# Sheet4.net
KiCad netlist of a schematic drawn in Altium Designer
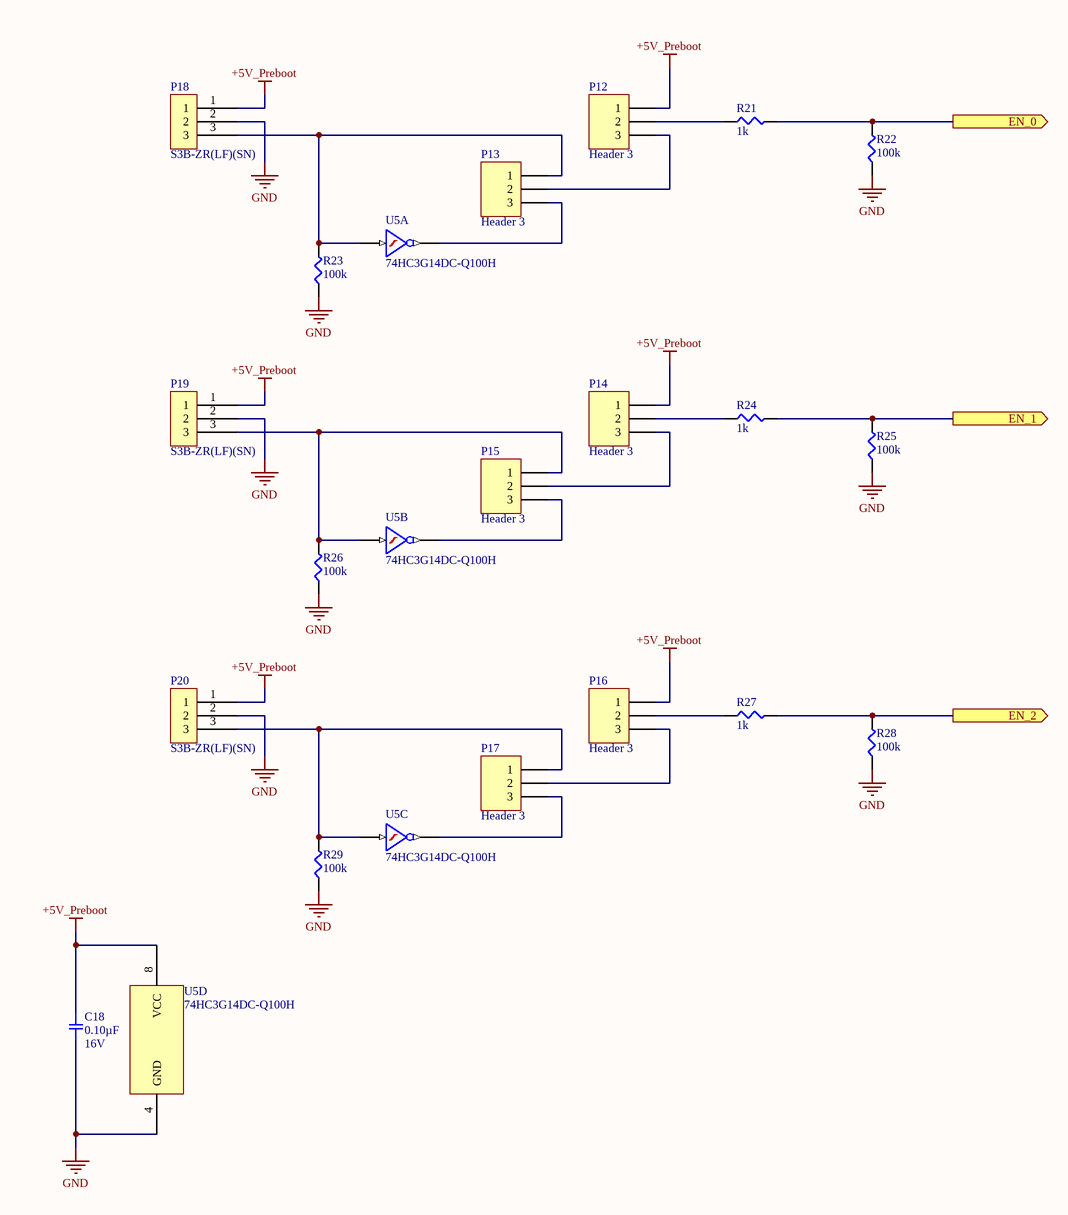
[diagram p0: Sheet4.SchDoc]

(export (version "E")
  (design (tool "Eeschema 10.0.6"))
  (components
    (comp (ref "C18")
      (value "0.10µF")
      (footprint "SMD-0402C")
      (description "CAP CER 0.1UF 16V X7R 0402")
      (fields
        (field (name "DIGI-KEY PART NUMBER") "490-4759-1-ND")
        (field (name "PART NUMBER") "GCM155R71C104KA55D")
        (field (name "VOLTAGE") "16V")
      )
      (libsource (lib "capacitor_murata_0402") (part "GCM155R71C104KA55D"))
    )
    (comp (ref "P12")
      (value "Header 3")
      (footprint "HDR1X3")
      (description "Header, 3-Pin")
      (fields (field (name "PUBLISHER") "Altium Limited"))
      (libsource (lib "Miscellaneous Connectors") (part "Header 3"))
    )
    (comp (ref "P13")
      (value "Header 3")
      (footprint "HDR1X3")
      (description "Header, 3-Pin")
      (fields (field (name "PUBLISHER") "Altium Limited"))
      (libsource (lib "Miscellaneous Connectors") (part "Header 3"))
    )
    (comp (ref "P14")
      (value "Header 3")
      (footprint "HDR1X3")
      (description "Header, 3-Pin")
      (fields (field (name "PUBLISHER") "Altium Limited"))
      (libsource (lib "Miscellaneous Connectors") (part "Header 3"))
    )
    (comp (ref "P15")
      (value "Header 3")
      (footprint "HDR1X3")
      (description "Header, 3-Pin")
      (fields (field (name "PUBLISHER") "Altium Limited"))
      (libsource (lib "Miscellaneous Connectors") (part "Header 3"))
    )
    (comp (ref "P16")
      (value "Header 3")
      (footprint "HDR1X3")
      (description "Header, 3-Pin")
      (fields (field (name "PUBLISHER") "Altium Limited"))
      (libsource (lib "Miscellaneous Connectors") (part "Header 3"))
    )
    (comp (ref "P17")
      (value "Header 3")
      (footprint "HDR1X3")
      (description "Header, 3-Pin")
      (fields (field (name "PUBLISHER") "Altium Limited"))
      (libsource (lib "Miscellaneous Connectors") (part "Header 3"))
    )
    (comp (ref "P18")
      (value "S3B-ZR(LF)(SN)")
      (footprint "S3B-ZR(LF)(SN)")
      (libsource (lib "ModularPayload") (part "S3B-ZR(LF)(SN)"))
    )
    (comp (ref "P19")
      (value "S3B-ZR(LF)(SN)")
      (footprint "S3B-ZR(LF)(SN)")
      (libsource (lib "ModularPayload") (part "S3B-ZR(LF)(SN)"))
    )
    (comp (ref "P20")
      (value "S3B-ZR(LF)(SN)")
      (footprint "S3B-ZR(LF)(SN)")
      (libsource (lib "ModularPayload") (part "S3B-ZR(LF)(SN)"))
    )
    (comp (ref "R21")
      (value "1k")
      (footprint "SMD-0402-RES")
      (description "RES SMD 1K OHM 5% 1/10W 0402")
      (fields (field (name "PART NUMBER") "ERJ-2GEJ102X") (field (name "DIGI-KEY PART NUMBER") "P1.0KJCT-ND"))
      (libsource (lib "Panasonic_ERJ_0402") (part "ERJ-2GEJ102X"))
    )
    (comp (ref "R22")
      (value "100k")
      (footprint "SMD-0402-RES")
      (description "RES SMD 100K OHM 5% 1/10W 0402")
      (fields (field (name "PART NUMBER") "ERJ-2GEJ104X") (field (name "DIGI-KEY PART NUMBER") "P100KJCT-ND"))
      (libsource (lib "Panasonic_ERJ_0402") (part "ERJ-2GEJ104X"))
    )
    (comp (ref "R23")
      (value "100k")
      (footprint "SMD-0402-RES")
      (description "RES SMD 100K OHM 5% 1/10W 0402")
      (fields (field (name "PART NUMBER") "ERJ-2GEJ104X") (field (name "DIGI-KEY PART NUMBER") "P100KJCT-ND"))
      (libsource (lib "Panasonic_ERJ_0402") (part "ERJ-2GEJ104X"))
    )
    (comp (ref "R24")
      (value "1k")
      (footprint "SMD-0402-RES")
      (description "RES SMD 1K OHM 5% 1/10W 0402")
      (fields (field (name "PART NUMBER") "ERJ-2GEJ102X") (field (name "DIGI-KEY PART NUMBER") "P1.0KJCT-ND"))
      (libsource (lib "Panasonic_ERJ_0402") (part "ERJ-2GEJ102X"))
    )
    (comp (ref "R25")
      (value "100k")
      (footprint "SMD-0402-RES")
      (description "RES SMD 100K OHM 5% 1/10W 0402")
      (fields (field (name "PART NUMBER") "ERJ-2GEJ104X") (field (name "DIGI-KEY PART NUMBER") "P100KJCT-ND"))
      (libsource (lib "Panasonic_ERJ_0402") (part "ERJ-2GEJ104X"))
    )
    (comp (ref "R26")
      (value "100k")
      (footprint "SMD-0402-RES")
      (description "RES SMD 100K OHM 5% 1/10W 0402")
      (fields (field (name "PART NUMBER") "ERJ-2GEJ104X") (field (name "DIGI-KEY PART NUMBER") "P100KJCT-ND"))
      (libsource (lib "Panasonic_ERJ_0402") (part "ERJ-2GEJ104X"))
    )
    (comp (ref "R27")
      (value "1k")
      (footprint "SMD-0402-RES")
      (description "RES SMD 1K OHM 5% 1/10W 0402")
      (fields (field (name "PART NUMBER") "ERJ-2GEJ102X") (field (name "DIGI-KEY PART NUMBER") "P1.0KJCT-ND"))
      (libsource (lib "Panasonic_ERJ_0402") (part "ERJ-2GEJ102X"))
    )
    (comp (ref "R28")
      (value "100k")
      (footprint "SMD-0402-RES")
      (description "RES SMD 100K OHM 5% 1/10W 0402")
      (fields (field (name "PART NUMBER") "ERJ-2GEJ104X") (field (name "DIGI-KEY PART NUMBER") "P100KJCT-ND"))
      (libsource (lib "Panasonic_ERJ_0402") (part "ERJ-2GEJ104X"))
    )
    (comp (ref "R29")
      (value "100k")
      (footprint "SMD-0402-RES")
      (description "RES SMD 100K OHM 5% 1/10W 0402")
      (fields (field (name "PART NUMBER") "ERJ-2GEJ104X") (field (name "DIGI-KEY PART NUMBER") "P100KJCT-ND"))
      (libsource (lib "Panasonic_ERJ_0402") (part "ERJ-2GEJ104X"))
    )
    (comp (ref "U5")
      (value "74HC3G14DC-Q100H")
      (footprint "TSSOP50P310X100-8N (74HC3G14DC-Q100H)")
      (libsource (lib "ModularPayload") (part "74HC3G14DC-Q100H"))
    )
  )
  (nets
    (net (code "1") (name "+5V_Preboot") (class "Default")
      (node (ref "C18") (pin "1") (pinfunction "1_1") (pintype "passive"))
      (node (ref "P12") (pin "1") (pinfunction "1_1") (pintype "passive"))
      (node (ref "P14") (pin "1") (pinfunction "1_1") (pintype "passive"))
      (node (ref "P16") (pin "1") (pinfunction "1_1") (pintype "passive"))
      (node (ref "P18") (pin "1") (pinfunction "1_1") (pintype "passive"))
      (node (ref "P19") (pin "1") (pinfunction "1_1") (pintype "passive"))
      (node (ref "P20") (pin "1") (pinfunction "1_1") (pintype "passive"))
      (node (ref "U5") (pin "8") (pinfunction "VCC_8") (pintype "passive"))
    )
    (net (code "2") (name "/EN_0") (class "Default")
      (node (ref "R21") (pin "2") (pinfunction "2_2") (pintype "passive"))
      (node (ref "R22") (pin "2") (pinfunction "2_2") (pintype "passive"))
    )
    (net (code "3") (name "/EN_1") (class "Default")
      (node (ref "R24") (pin "2") (pinfunction "2_2") (pintype "passive"))
      (node (ref "R25") (pin "2") (pinfunction "2_2") (pintype "passive"))
    )
    (net (code "4") (name "/EN_2") (class "Default")
      (node (ref "R27") (pin "2") (pinfunction "2_2") (pintype "passive"))
      (node (ref "R28") (pin "2") (pinfunction "2_2") (pintype "passive"))
    )
    (net (code "5") (name "GND") (class "Default")
      (node (ref "C18") (pin "2") (pinfunction "2_2") (pintype "passive"))
      (node (ref "P18") (pin "2") (pinfunction "2_2") (pintype "passive"))
      (node (ref "P19") (pin "2") (pinfunction "2_2") (pintype "passive"))
      (node (ref "P20") (pin "2") (pinfunction "2_2") (pintype "passive"))
      (node (ref "R22") (pin "1") (pinfunction "1_1") (pintype "passive"))
      (node (ref "R23") (pin "1") (pinfunction "1_1") (pintype "passive"))
      (node (ref "R25") (pin "1") (pinfunction "1_1") (pintype "passive"))
      (node (ref "R26") (pin "1") (pinfunction "1_1") (pintype "passive"))
      (node (ref "R28") (pin "1") (pinfunction "1_1") (pintype "passive"))
      (node (ref "R29") (pin "1") (pinfunction "1_1") (pintype "passive"))
      (node (ref "U5") (pin "4") (pinfunction "GND_4") (pintype "passive"))
    )
    (net (code "6") (name "Net-(P12-Pad2)") (class "Default")
      (node (ref "P12") (pin "2") (pinfunction "2_2") (pintype "passive"))
      (node (ref "R21") (pin "1") (pinfunction "1_1") (pintype "passive"))
    )
    (net (code "7") (name "Net-(P12-Pad3)") (class "Default")
      (node (ref "P12") (pin "3") (pinfunction "3_3") (pintype "passive"))
      (node (ref "P13") (pin "2") (pinfunction "2_2") (pintype "passive"))
    )
    (net (code "8") (name "Net-(P14-Pad2)") (class "Default")
      (node (ref "P14") (pin "2") (pinfunction "2_2") (pintype "passive"))
      (node (ref "R24") (pin "1") (pinfunction "1_1") (pintype "passive"))
    )
    (net (code "9") (name "Net-(P14-Pad3)") (class "Default")
      (node (ref "P14") (pin "3") (pinfunction "3_3") (pintype "passive"))
      (node (ref "P15") (pin "2") (pinfunction "2_2") (pintype "passive"))
    )
    (net (code "10") (name "Net-(P16-Pad2)") (class "Default")
      (node (ref "P16") (pin "2") (pinfunction "2_2") (pintype "passive"))
      (node (ref "R27") (pin "1") (pinfunction "1_1") (pintype "passive"))
    )
    (net (code "11") (name "Net-(P16-Pad3)") (class "Default")
      (node (ref "P16") (pin "3") (pinfunction "3_3") (pintype "passive"))
      (node (ref "P17") (pin "2") (pinfunction "2_2") (pintype "passive"))
    )
    (net (code "12") (name "Net-(U5A-1A)") (class "Default")
      (node (ref "P13") (pin "1") (pinfunction "1_1") (pintype "passive"))
      (node (ref "P18") (pin "3") (pinfunction "3_3") (pintype "passive"))
      (node (ref "R23") (pin "2") (pinfunction "2_2") (pintype "passive"))
      (node (ref "U5") (pin "1") (pinfunction "1A_1") (pintype "input"))
    )
    (net (code "13") (name "Net-(U5A-1Y)") (class "Default")
      (node (ref "P13") (pin "3") (pinfunction "3_3") (pintype "passive"))
      (node (ref "U5") (pin "7") (pinfunction "1Y_7") (pintype "output"))
    )
    (net (code "14") (name "Net-(U5B-2A)") (class "Default")
      (node (ref "P15") (pin "1") (pinfunction "1_1") (pintype "passive"))
      (node (ref "P19") (pin "3") (pinfunction "3_3") (pintype "passive"))
      (node (ref "R26") (pin "2") (pinfunction "2_2") (pintype "passive"))
      (node (ref "U5") (pin "3") (pinfunction "2A_3") (pintype "input"))
    )
    (net (code "15") (name "Net-(U5B-2Y)") (class "Default")
      (node (ref "P15") (pin "3") (pinfunction "3_3") (pintype "passive"))
      (node (ref "U5") (pin "5") (pinfunction "2Y_5") (pintype "output"))
    )
    (net (code "16") (name "Net-(U5C-3A)") (class "Default")
      (node (ref "P17") (pin "1") (pinfunction "1_1") (pintype "passive"))
      (node (ref "P20") (pin "3") (pinfunction "3_3") (pintype "passive"))
      (node (ref "R29") (pin "2") (pinfunction "2_2") (pintype "passive"))
      (node (ref "U5") (pin "6") (pinfunction "3A_6") (pintype "input"))
    )
    (net (code "17") (name "Net-(U5C-3Y)") (class "Default")
      (node (ref "P17") (pin "3") (pinfunction "3_3") (pintype "passive"))
      (node (ref "U5") (pin "2") (pinfunction "3Y_2") (pintype "output"))
    )
  )
)
